# v009_schematics.net
KiCad netlist of a schematic drawn in Altium Designer
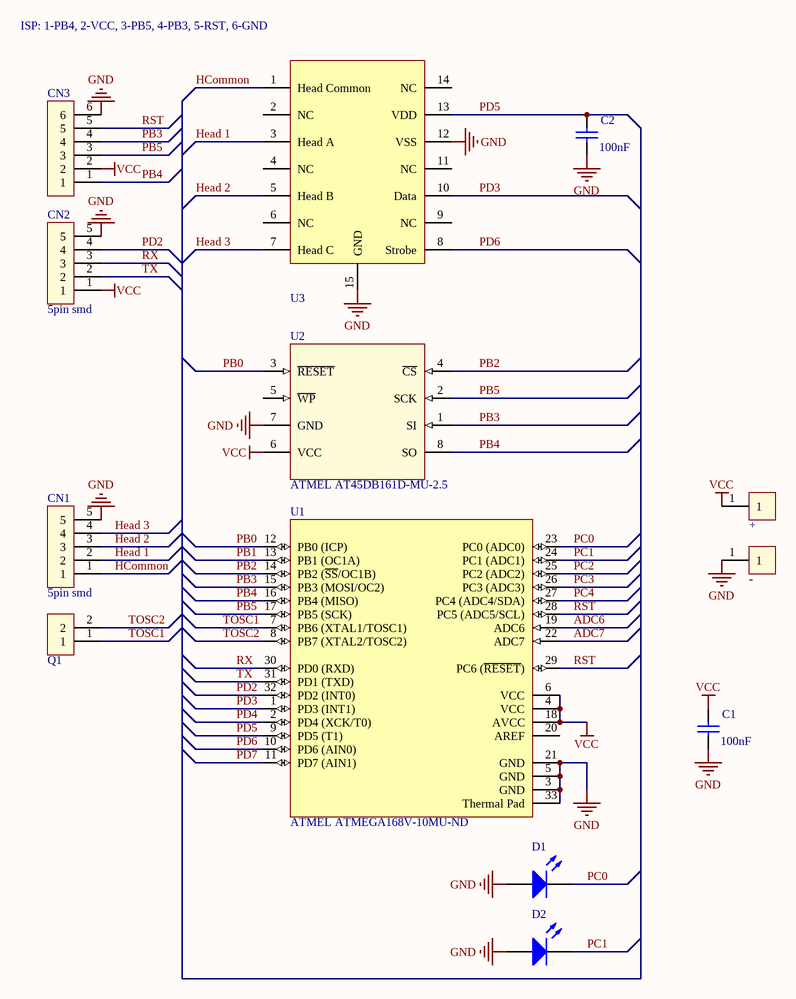
[diagram p0: v009 schematics.SCHDOC]

(export (version "E")
  (design (tool "Eeschema 10.0.6"))
  (components
    (comp (ref "+")
      (value "No component mounted")
      (footprint "SU01LS")
      (libsource (lib "*") (part "1pin smd"))
    )
    (comp (ref "-")
      (value "No component mounted")
      (footprint "SU01LS")
      (libsource (lib "*") (part "1pin smd"))
    )
    (comp (ref "C1")
      (value "100nF")
      (footprint "CC0603(0201)")
      (description "100nf Capacitor - Footprint CC0603 (0201)")
      (fields
        (field (name "DIGI-KEY PART NUMBER") "490-3167-1-ND")
        (field (name "MANUFACTURER") "Murata Electronics")
        (field (name "PUBLISHER") "Altium Limited")
      )
      (libsource (lib "Miscellaneous Devices") (part "Cap"))
    )
    (comp (ref "C2")
      (value "100nF")
      (footprint "CC0603(0201)")
      (description "CAP CER .1UF 6.3V X5R 0201")
      (fields
        (field (name "DIGI-KEY PART NUMBER") "490-3167-1-ND")
        (field (name "PUBLISHER") "Altium Limited")
      )
      (libsource (lib "Miscellaneous Devices") (part "Cap"))
    )
    (comp (ref "CN1")
      (value "5pin smd")
      (footprint "SU05LSR wide")
      (description "No component mounted")
      (libsource (lib "v4lib") (part "5pin smd"))
    )
    (comp (ref "CN2")
      (value "5pin smd")
      (footprint "SU05LSR wide")
      (description "No component mounted")
      (libsource (lib "v4lib") (part "5pin smd"))
    )
    (comp (ref "CN3")
      (value "No component mounted")
      (footprint "SU06LST FULL")
      (libsource (lib "v4lib") (part "6pin smd"))
    )
    (comp (ref "D1")
      (value "LED1")
      (footprint "CC1005(0402)")
      (description "LED 0402 GREEN 465NM TRANSPARENT")
      (fields
        (field (name "DIGI-KEY PART NUMBER") "511-1615-1-ND")
        (field (name "MANUFACTURER") "Rohm Semiconductor")
        (field (name "PUBLISHER") "Altium Limited")
      )
      (libsource (lib "Miscellaneous Devices") (part "LED3"))
    )
    (comp (ref "D2")
      (value "LED1")
      (footprint "CC1005(0402)")
      (description "LED 0402 RED 465NM TRANSPARENT")
      (fields
        (field (name "DIGI-KEY PART NUMBER") "511-1615-1-ND")
        (field (name "MANUFACTURER") "Rohm Semiconductor")
        (field (name "PUBLISHER") "Altium Limited")
      )
      (libsource (lib "Miscellaneous Devices") (part "LED3"))
    )
    (comp (ref "Q1")
      (value "32.768khz crystal 1.5 x 3.2mm")
      (footprint "Quartz SMD (small)")
      (description "CRYSTAL 32.768KHZ 1.5 x 3.2mm")
      (fields
        (field (name "DIGI-KEY PART NUMBER") "535-9542-1-ND")
        (field (name "MANUFACTURER") "Abracon Corporation")
      )
      (libsource (lib "v4lib") (part "2pin smd"))
    )
    (comp (ref "U1")
      (value "ATMEL ATMEGA168V-10MU-ND")
      (footprint "32M1-A L 3")
      (description "ATMEL ATMEGA168V-10MU")
      (fields
        (field (name "DIGI-KEY PART NUMBER") "ATMEGA168V-10MU-ND")
        (field (name "MANUFACTURER") "ATMEL")
        (field (name "PUBLISHER") "Altium Limited")
      )
      (libsource (lib "Atmel Microcontroller 8-Bit AVR") (part "ATmega8L-8MC"))
    )
    (comp (ref "U2")
      (value "ATMEL AT45DB161D-MU-2.5")
      (footprint "8m1-a mlf 3")
      (description "ATMEL AT45DB321D-MU")
      (fields
        (field (name "DIGI-KEY PART NUMBER") "AT45DB161D-MU-2.5-ND")
        (field (name "MANUFACTURER") "ATMEL")
      )
      (libsource (lib "v4lib") (part "at45db041b"))
    )
    (comp (ref "U3")
      (value "Asic 3V MLF14")
      (footprint "delta asic - 5")
      (fields (field (name "MANUFACTURER") "Magtek") (field (name "MANUFACTURER PART NUMBER") "21006540"))
      (libsource (lib "v4lib") (part "delta asic 3volt"))
    )
  )
  (nets
    (net (code "1") (name "/ADC6") (class "Default")
      (node (ref "U1") (pin "19") (pinfunction "ADC6_19") (pintype "input"))
    )
    (net (code "2") (name "/ADC7") (class "Default")
      (node (ref "U1") (pin "22") (pinfunction "ADC7_22") (pintype "input"))
    )
    (net (code "3") (name "/HCommon") (class "Default")
      (node (ref "CN1") (pin "1") (pinfunction "1_1") (pintype "passive"))
      (node (ref "U3") (pin "1") (pinfunction "Head_Common_1") (pintype "passive"))
    )
    (net (code "4") (name "/Head 1") (class "Default")
      (node (ref "CN1") (pin "2") (pinfunction "2_2") (pintype "passive"))
      (node (ref "U3") (pin "3") (pinfunction "Head_A_3") (pintype "passive"))
    )
    (net (code "5") (name "/Head 2") (class "Default")
      (node (ref "CN1") (pin "3") (pinfunction "3_3") (pintype "passive"))
      (node (ref "U3") (pin "5") (pinfunction "Head_B_5") (pintype "passive"))
    )
    (net (code "6") (name "/Head 3") (class "Default")
      (node (ref "CN1") (pin "4") (pinfunction "4_4") (pintype "passive"))
      (node (ref "U3") (pin "7") (pinfunction "Head_C_7") (pintype "passive"))
    )
    (net (code "7") (name "/PB0") (class "Default")
      (node (ref "U1") (pin "12") (pinfunction "PB0_(ICP)_12") (pintype "bidirectional"))
      (node (ref "U2") (pin "3") (pinfunction "~{RESET}_3") (pintype "input"))
    )
    (net (code "8") (name "/PB1") (class "Default")
      (node (ref "U1") (pin "13") (pinfunction "PB1_(OC1A)_13") (pintype "bidirectional"))
    )
    (net (code "9") (name "/PB2") (class "Default")
      (node (ref "U1") (pin "14") (pinfunction "PB2_(~{SS}/OC1B)_14") (pintype "bidirectional"))
      (node (ref "U2") (pin "4") (pinfunction "~{CS}_4") (pintype "input"))
    )
    (net (code "10") (name "/PB3") (class "Default")
      (node (ref "CN3") (pin "4") (pinfunction "4_4") (pintype "passive"))
      (node (ref "U1") (pin "15") (pinfunction "PB3_(MOSI/OC2)_15") (pintype "bidirectional"))
      (node (ref "U2") (pin "1") (pinfunction "SI_1") (pintype "input"))
    )
    (net (code "11") (name "/PB4") (class "Default")
      (node (ref "CN3") (pin "1") (pinfunction "1_1") (pintype "passive"))
      (node (ref "U1") (pin "16") (pinfunction "PB4_(MISO)_16") (pintype "bidirectional"))
      (node (ref "U2") (pin "8") (pinfunction "SO_8") (pintype "passive"))
    )
    (net (code "12") (name "/PB5") (class "Default")
      (node (ref "CN3") (pin "3") (pinfunction "3_3") (pintype "passive"))
      (node (ref "U1") (pin "17") (pinfunction "PB5_(SCK)_17") (pintype "bidirectional"))
      (node (ref "U2") (pin "2") (pinfunction "SCK_2") (pintype "input"))
    )
    (net (code "13") (name "/PC0") (class "Default")
      (node (ref "D1") (pin "2") (pinfunction "K_2") (pintype "passive"))
      (node (ref "U1") (pin "23") (pinfunction "PC0_(ADC0)_23") (pintype "bidirectional"))
    )
    (net (code "14") (name "/PC1") (class "Default")
      (node (ref "D2") (pin "2") (pinfunction "K_2") (pintype "passive"))
      (node (ref "U1") (pin "24") (pinfunction "PC1_(ADC1)_24") (pintype "bidirectional"))
    )
    (net (code "15") (name "/PC2") (class "Default")
      (node (ref "U1") (pin "25") (pinfunction "PC2_(ADC2)_25") (pintype "bidirectional"))
    )
    (net (code "16") (name "/PC3") (class "Default")
      (node (ref "U1") (pin "26") (pinfunction "PC3_(ADC3)_26") (pintype "bidirectional"))
    )
    (net (code "17") (name "/PC4") (class "Default")
      (node (ref "U1") (pin "27") (pinfunction "PC4_(ADC4/SDA)_27") (pintype "bidirectional"))
    )
    (net (code "18") (name "/PD2") (class "Default")
      (node (ref "CN2") (pin "4") (pinfunction "4_4") (pintype "passive"))
      (node (ref "U1") (pin "32") (pinfunction "PD2_(INT0)_32") (pintype "bidirectional"))
    )
    (net (code "19") (name "/PD3") (class "Default")
      (node (ref "U1") (pin "1") (pinfunction "PD3_(INT1)_1") (pintype "bidirectional"))
      (node (ref "U3") (pin "10") (pinfunction "Data_10") (pintype "passive"))
    )
    (net (code "20") (name "/PD4") (class "Default")
      (node (ref "U1") (pin "2") (pinfunction "PD4_(XCK/T0)_2") (pintype "bidirectional"))
    )
    (net (code "21") (name "/PD5") (class "Default")
      (node (ref "C2") (pin "1") (pinfunction "1_1") (pintype "passive"))
      (node (ref "U1") (pin "9") (pinfunction "PD5_(T1)_9") (pintype "bidirectional"))
      (node (ref "U3") (pin "13") (pinfunction "VDD_13") (pintype "passive"))
    )
    (net (code "22") (name "/PD6") (class "Default")
      (node (ref "U1") (pin "10") (pinfunction "PD6_(AIN0)_10") (pintype "bidirectional"))
      (node (ref "U3") (pin "8") (pinfunction "Strobe_8") (pintype "passive"))
    )
    (net (code "23") (name "/PD7") (class "Default")
      (node (ref "U1") (pin "11") (pinfunction "PD7_(AIN1)_11") (pintype "bidirectional"))
    )
    (net (code "24") (name "/RST") (class "Default")
      (node (ref "CN3") (pin "5") (pinfunction "5_5") (pintype "passive"))
      (node (ref "U1") (pin "28") (pinfunction "PC5_(ADC5/SCL)_28") (pintype "bidirectional"))
      (node (ref "U1") (pin "29") (pinfunction "PC6_(~{RESET})_29") (pintype "bidirectional"))
    )
    (net (code "25") (name "/RX") (class "Default")
      (node (ref "CN2") (pin "3") (pinfunction "3_3") (pintype "passive"))
      (node (ref "U1") (pin "30") (pinfunction "PD0_(RXD)_30") (pintype "bidirectional"))
    )
    (net (code "26") (name "/TOSC1") (class "Default")
      (node (ref "Q1") (pin "1") (pinfunction "1_1") (pintype "passive"))
      (node (ref "U1") (pin "7") (pinfunction "PB6_(XTAL1/TOSC1)_7") (pintype "bidirectional"))
    )
    (net (code "27") (name "/TOSC2") (class "Default")
      (node (ref "Q1") (pin "2") (pinfunction "2_2") (pintype "passive"))
      (node (ref "U1") (pin "8") (pinfunction "PB7_(XTAL2/TOSC2)_8") (pintype "bidirectional"))
    )
    (net (code "28") (name "/TX") (class "Default")
      (node (ref "CN2") (pin "2") (pinfunction "2_2") (pintype "passive"))
      (node (ref "U1") (pin "31") (pinfunction "PD1_(TXD)_31") (pintype "bidirectional"))
    )
    (net (code "29") (name "GND") (class "Default")
      (node (ref "-") (pin "1") (pinfunction "1_1") (pintype "passive"))
      (node (ref "C1") (pin "2") (pinfunction "2_2") (pintype "passive"))
      (node (ref "C2") (pin "2") (pinfunction "2_2") (pintype "passive"))
      (node (ref "CN1") (pin "5") (pinfunction "5_5") (pintype "passive"))
      (node (ref "CN2") (pin "5") (pinfunction "5_5") (pintype "passive"))
      (node (ref "CN3") (pin "6") (pinfunction "6_6") (pintype "passive"))
      (node (ref "D1") (pin "1") (pinfunction "A_1") (pintype "passive"))
      (node (ref "D2") (pin "1") (pinfunction "A_1") (pintype "passive"))
      (node (ref "U1") (pin "21") (pinfunction "GND_21") (pintype "power_in"))
      (node (ref "U1") (pin "3") (pinfunction "GND_3") (pintype "power_in"))
      (node (ref "U1") (pin "33") (pinfunction "Thermal_Pad_33") (pintype "power_in"))
      (node (ref "U1") (pin "5") (pinfunction "GND_5") (pintype "power_in"))
      (node (ref "U2") (pin "7") (pinfunction "GND_7") (pintype "passive"))
      (node (ref "U3") (pin "12") (pinfunction "VSS_12") (pintype "passive"))
      (node (ref "U3") (pin "15") (pinfunction "GND_15") (pintype "passive"))
    )
    (net (code "30") (name "VCC") (class "Default")
      (node (ref "+") (pin "1") (pinfunction "1_1") (pintype "passive"))
      (node (ref "C1") (pin "1") (pinfunction "1_1") (pintype "passive"))
      (node (ref "CN2") (pin "1") (pinfunction "1_1") (pintype "passive"))
      (node (ref "CN3") (pin "2") (pinfunction "2_2") (pintype "passive"))
      (node (ref "U1") (pin "18") (pinfunction "AVCC_18") (pintype "power_in"))
      (node (ref "U1") (pin "4") (pinfunction "VCC_4") (pintype "power_in"))
      (node (ref "U1") (pin "6") (pinfunction "VCC_6") (pintype "power_in"))
      (node (ref "U2") (pin "6") (pinfunction "VCC_6") (pintype "power_in"))
    )
    (net (code "31") (name "unconnected-(U1-AREF-Pad20)") (class "Default")
      (node (ref "U1") (pin "20") (pinfunction "AREF_20") (pintype "passive"))
    )
    (net (code "32") (name "unconnected-(U2-~{WP}-Pad5)") (class "Default")
      (node (ref "U2") (pin "5") (pinfunction "~{WP}_5") (pintype "input"))
    )
    (net (code "33") (name "unconnected-(U3-NC-Pad2)") (class "Default")
      (node (ref "U3") (pin "2") (pinfunction "NC_2") (pintype "passive"))
    )
    (net (code "34") (name "unconnected-(U3-NC-Pad4)") (class "Default")
      (node (ref "U3") (pin "4") (pinfunction "NC_4") (pintype "passive"))
    )
    (net (code "35") (name "unconnected-(U3-NC-Pad6)") (class "Default")
      (node (ref "U3") (pin "6") (pinfunction "NC_6") (pintype "passive"))
    )
    (net (code "36") (name "unconnected-(U3-NC-Pad9)") (class "Default")
      (node (ref "U3") (pin "9") (pinfunction "NC_9") (pintype "passive"))
    )
    (net (code "37") (name "unconnected-(U3-NC-Pad11)") (class "Default")
      (node (ref "U3") (pin "11") (pinfunction "NC_11") (pintype "passive"))
    )
    (net (code "38") (name "unconnected-(U3-NC-Pad14)") (class "Default")
      (node (ref "U3") (pin "14") (pinfunction "NC_14") (pintype "passive"))
    )
  )
)
